# Data_Board_Solo.net
KiCad netlist of a schematic drawn in EAGLE
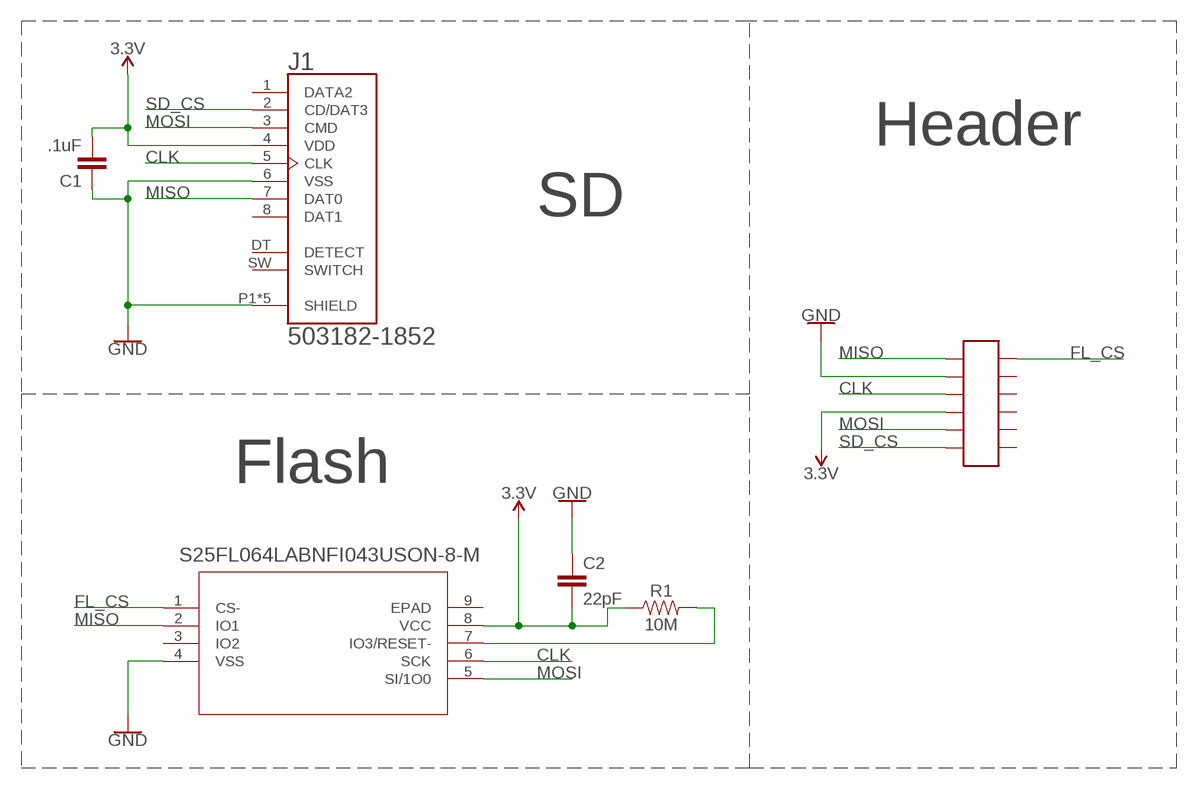
[diagram p0: schematic, sheet 1]

(export (version "E")
  (design (tool "Eeschema 10.0.6"))
  (components
    (comp (ref "C1")
      (value ".1uF")
      (footprint "eagle-import:0603")
      (libsource (lib "eagle-import") (part "10NF-0603-50V-10%"))
    )
    (comp (ref "C2")
      (value "22pF")
      (footprint "eagle-import:0603")
      (libsource (lib "eagle-import") (part "10NF-0603-50V-10%"))
    )
    (comp (ref "J1")
      (value "503182-1852")
      (footprint "eagle-import:MOLEX_503182-1852")
      (fields
        (field (name "DIGI-KEY_PART_NUMBER") "WM12834CT-ND")
        (field (name "MF") "Molex")
        (field (name "MP") "5031821852")
      )
      (libsource (lib "eagle-import") (part "503182-1852"))
    )
    (comp (ref "R1")
      (value "10M")
      (footprint "eagle-import:0603")
      (libsource (lib "eagle-import") (part "220KOHM-0603-1/10W-1%"))
    )
    (comp (ref "U$1")
      (value "12POS_HEADER")
      (footprint "eagle-import:12POS_HEADER")
      (libsource (lib "eagle-import") (part "12POS_HEADER"))
    )
    (comp (ref "U1")
      (value "S25FL064LABNFI043USON-8-M")
      (footprint "eagle-import:USON-8-M")
      (fields
        (field (name "MANUFACTURER_PART_NUMBER") "S25FL064LABNFI043")
        (field (name "COPYRIGHT") "Copyright (C) 2018 Accelerated Designs. All rights reserved")
      )
      (libsource (lib "eagle-import") (part "S25FL064LABNFI043USON-8-M"))
    )
  )
  (nets
    (net (code "1") (name "/CLK") (class "Default")
      (node (ref "J1") (pin "5") (pinfunction "CLK_5") (pintype "bidirectional"))
      (node (ref "U$1") (pin "P$3") (pinfunction "P$3_P$3") (pintype "bidirectional"))
      (node (ref "U1") (pin "6") (pinfunction "SCK_6") (pintype "passive"))
    )
    (net (code "2") (name "/FL_CS") (class "Default")
      (node (ref "U$1") (pin "P$12") (pinfunction "P$12_P$12") (pintype "bidirectional"))
      (node (ref "U1") (pin "1") (pinfunction "CS-_1") (pintype "passive"))
    )
    (net (code "3") (name "/MISO") (class "Default")
      (node (ref "J1") (pin "7") (pinfunction "DAT0_7") (pintype "bidirectional"))
      (node (ref "U$1") (pin "P$1") (pinfunction "P$1_P$1") (pintype "bidirectional"))
      (node (ref "U1") (pin "2") (pinfunction "IO1_2") (pintype "bidirectional"))
    )
    (net (code "4") (name "/MOSI") (class "Default")
      (node (ref "J1") (pin "3") (pinfunction "CMD_3") (pintype "bidirectional"))
      (node (ref "U$1") (pin "P$5") (pinfunction "P$5_P$5") (pintype "bidirectional"))
      (node (ref "U1") (pin "5") (pinfunction "SI/1O0_5") (pintype "passive"))
    )
    (net (code "5") (name "/SD_CS") (class "Default")
      (node (ref "J1") (pin "2") (pinfunction "CD/DAT3_2") (pintype "bidirectional"))
      (node (ref "U$1") (pin "P$6") (pinfunction "P$6_P$6") (pintype "bidirectional"))
    )
    (net (code "6") (name "3.3V") (class "Default")
      (node (ref "C1") (pin "2") (pinfunction "2_2") (pintype "passive"))
      (node (ref "C2") (pin "2") (pinfunction "2_2") (pintype "passive"))
      (node (ref "J1") (pin "4") (pinfunction "VDD_4") (pintype "power_in"))
      (node (ref "R1") (pin "1") (pinfunction "1_1") (pintype "passive"))
      (node (ref "U$1") (pin "P$4") (pinfunction "P$4_P$4") (pintype "bidirectional"))
      (node (ref "U1") (pin "8") (pinfunction "VCC_8") (pintype "power_in"))
    )
    (net (code "7") (name "GND") (class "Default")
      (node (ref "C1") (pin "1") (pinfunction "1_1") (pintype "passive"))
      (node (ref "C2") (pin "1") (pinfunction "1_1") (pintype "passive"))
      (node (ref "J1") (pin "6") (pinfunction "VSS_6") (pintype "power_in"))
      (node (ref "J1") (pin "P1") (pinfunction "SHIELD_P1") (pintype "passive"))
      (node (ref "J1") (pin "P2") (pinfunction "SHIELD_P2") (pintype "passive"))
      (node (ref "J1") (pin "P3") (pinfunction "SHIELD_P3") (pintype "passive"))
      (node (ref "J1") (pin "P4") (pinfunction "SHIELD_P4") (pintype "passive"))
      (node (ref "J1") (pin "P5") (pinfunction "SHIELD_P5") (pintype "passive"))
      (node (ref "U$1") (pin "P$2") (pinfunction "P$2_P$2") (pintype "bidirectional"))
      (node (ref "U1") (pin "4") (pinfunction "VSS_4") (pintype "passive"))
    )
    (net (code "8") (name "Net-(U1-IO3{slash}RESET-)") (class "Default")
      (node (ref "R1") (pin "2") (pinfunction "2_2") (pintype "passive"))
      (node (ref "U1") (pin "7") (pinfunction "IO3/RESET-_7") (pintype "bidirectional"))
    )
    (net (code "9") (name "unconnected-(J1-DAT1-Pad8)") (class "Default")
      (node (ref "J1") (pin "8") (pinfunction "DAT1_8") (pintype "bidirectional"))
    )
    (net (code "10") (name "unconnected-(J1-DATA2-Pad1)") (class "Default")
      (node (ref "J1") (pin "1") (pinfunction "DATA2_1") (pintype "bidirectional"))
    )
    (net (code "11") (name "unconnected-(J1-DETECT-PadDT)") (class "Default")
      (node (ref "J1") (pin "DT") (pinfunction "DETECT_DT") (pintype "bidirectional"))
    )
    (net (code "12") (name "unconnected-(J1-SWITCH-PadSW)") (class "Default")
      (node (ref "J1") (pin "SW") (pinfunction "SWITCH_SW") (pintype "bidirectional"))
    )
    (net (code "13") (name "unconnected-(U$1-PadP$7)") (class "Default")
      (node (ref "U$1") (pin "P$7") (pinfunction "P$7_P$7") (pintype "bidirectional"))
    )
    (net (code "14") (name "unconnected-(U$1-PadP$8)") (class "Default")
      (node (ref "U$1") (pin "P$8") (pinfunction "P$8_P$8") (pintype "bidirectional"))
    )
    (net (code "15") (name "unconnected-(U$1-PadP$9)") (class "Default")
      (node (ref "U$1") (pin "P$9") (pinfunction "P$9_P$9") (pintype "bidirectional"))
    )
    (net (code "16") (name "unconnected-(U$1-PadP$10)") (class "Default")
      (node (ref "U$1") (pin "P$10") (pinfunction "P$10_P$10") (pintype "bidirectional"))
    )
    (net (code "17") (name "unconnected-(U$1-PadP$11)") (class "Default")
      (node (ref "U$1") (pin "P$11") (pinfunction "P$11_P$11") (pintype "bidirectional"))
    )
    (net (code "18") (name "unconnected-(U1-EPAD-Pad9)") (class "Default")
      (node (ref "U1") (pin "9") (pinfunction "EPAD_9") (pintype "passive"))
    )
    (net (code "19") (name "unconnected-(U1-IO2-Pad3)") (class "Default")
      (node (ref "U1") (pin "3") (pinfunction "IO2_3") (pintype "bidirectional"))
    )
  )
)
